# DCDC-LMR16030.net
KiCad netlist of a schematic drawn in Altium Designer
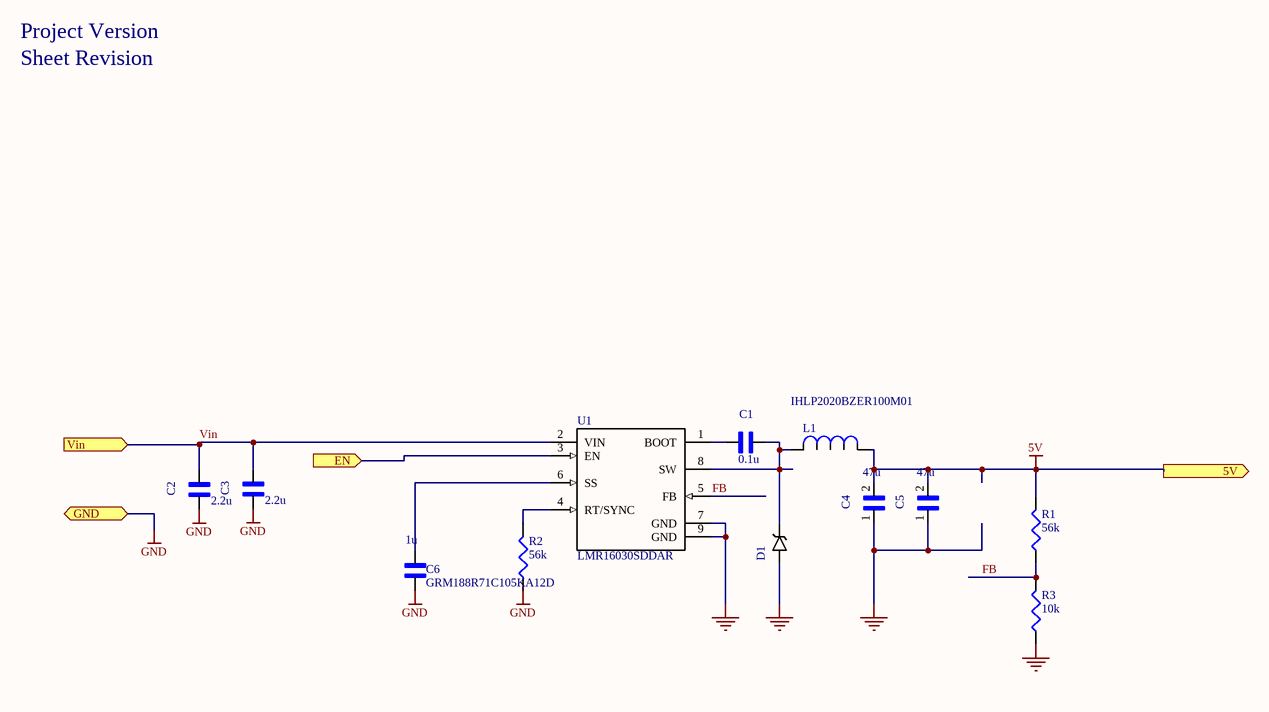
[diagram p0: DCDC-LMR16030.SchDoc]

(export (version "E")
  (design (tool "Eeschema 10.0.6"))
  (components
    (comp (ref "C1")
      (value "0.1u")
      (footprint "*CAPC1608X90")
      (description "Cap Thin Film 0.1uf 50v 0603")
      (fields (field (name "MF") "AVX") (field (name "MP") "GX035C104MAT2-500 or CL10B104JB8NNNC"))
      (libsource (lib "lib") (part "GX035C104MAT2-500"))
    )
    (comp (ref "C2")
      (value "2.2u")
      (footprint "*CAP3216X125N")
      (description "1206 2.2 uF 50 V В±10% Tolerance X7R SMT Multilayer Ceramic Capacitor")
      (fields (field (name "MF") "Murata Electronics") (field (name "MP") "GRM31CR71H225KA88L"))
      (libsource (lib "lib") (part "GRM31CR71H225KA88L"))
    )
    (comp (ref "C3")
      (value "2.2u")
      (footprint "*CAP3216X125N")
      (description "1206 2.2 uF 50 V В±10% Tolerance X7R SMT Multilayer Ceramic Capacitor")
      (fields (field (name "MF") "Murata Electronics") (field (name "MP") "GRM31CR71H225KA88L"))
      (libsource (lib "lib") (part "GRM31CR71H225KA88L"))
    )
    (comp (ref "C4")
      (value "47u")
      (footprint "*CAPC3216X125N")
      (description "Multilayer Ceramic Capacitor, GRM Series, 47 - F, - 10%, X5R, 10 V, 1206 [3216 Metric]")
      (fields (field (name "MF") "Murata Electronics") (field (name "MP") "GRM31CR61A476KE15L"))
      (libsource (lib "lib") (part "GRM31CR61A476KE15L"))
    )
    (comp (ref "C5")
      (value "47u")
      (footprint "*CAPC3216X125N")
      (description "Multilayer Ceramic Capacitor, GRM Series, 47 - F, - 10%, X5R, 10 V, 1206 [3216 Metric]")
      (fields (field (name "MF") "Murata Electronics") (field (name "MP") "GRM31CR61A476KE15L"))
      (libsource (lib "lib") (part "GRM31CR61A476KE15L"))
    )
    (comp (ref "C6")
      (value "GRM188R71C105KA12D")
      (footprint "CAPC1608X90N")
      (description "SMD Capacitor X7R(EIA) with Capacitance: 1.0uF Tol. 10%. Rated Voltage: 16Vdc")
      (fields (field (name "MF") "Murata Electronics") (field (name "ALTIUM_VALUE") "1u"))
      (libsource (lib "lib") (part "GRM188R71C105KA12D"))
    )
    (comp (ref "D1")
      (value "SK56")
      (footprint "*SMB_P6SMB62AT3G(Primary)")
      (description "Диод Шоттки 5А 60В [SMB / DO-214AA]")
      (fields (field (name "MF") "Littelfuse Inc."))
      (libsource (lib "lib") (part "SK56"))
    )
    (comp (ref "L1")
      (value "IHLP2020BZER100M01")
      (footprint "IHLP")
      (description "10ÂµH Shielded Molded Inductor 2.3A 199mOhm Max Nonstandard")
      (fields (field (name "MF") "Vishay Dale"))
      (libsource (lib "lib") (part "IHLP2020BZER100M01"))
    )
    (comp (ref "R1")
      (value "56k")
      (footprint "J1-0603")
      (description "Resistor")
      (fields (field (name "MP") "RC0603FR-0756KL") (field (name "Comment") "Res3"))
      (libsource (lib "Miscellaneous Devices") (part "Res3"))
    )
    (comp (ref "R2")
      (value "56k")
      (footprint "J1-0603")
      (description "Resistor")
      (fields (field (name "MP") "RC0603FR-0756KL") (field (name "Comment") "Res3"))
      (libsource (lib "Miscellaneous Devices") (part "Res3"))
    )
    (comp (ref "R3")
      (value "10k")
      (footprint "J1-0603")
      (description "10 kOhms 1 0.1 W 1 10 W Chip Resistor 0603 1608 Metric Thick Film")
      (fields (field (name "MF") "Yageo or NXP") (field (name "MP") "10K 1% 0603"))
      (libsource (lib "CAN_NODE_MINI") (part "RC0603FR-0710KL"))
    )
    (comp (ref "U1")
      (value "LMR16030SDDAR")
      (footprint "*SOIC127P600X170-9N - duplicate")
      (fields (field (name "MF") "Texas Instruments"))
      (libsource (lib "lib") (part "LMR16030SDDAR"))
    )
  )
  (nets
    (net (code "1") (name "/EN") (class "Default")
      (node (ref "U1") (pin "3") (pinfunction "EN_3") (pintype "input"))
    )
    (net (code "2") (name "/FB") (class "Default")
      (node (ref "R1") (pin "1") (pinfunction "1_1") (pintype "passive"))
      (node (ref "R3") (pin "2") (pinfunction "2_2") (pintype "passive"))
      (node (ref "U1") (pin "5") (pinfunction "FB_5") (pintype "input"))
    )
    (net (code "3") (name "/Vin") (class "Default")
      (node (ref "C2") (pin "1") (pinfunction "1_1") (pintype "passive"))
      (node (ref "C3") (pin "1") (pinfunction "1_1") (pintype "passive"))
      (node (ref "U1") (pin "2") (pinfunction "VIN_2") (pintype "power_in"))
    )
    (net (code "4") (name "5V") (class "Default")
      (node (ref "C4") (pin "2") (pinfunction "2_2") (pintype "passive"))
      (node (ref "C5") (pin "2") (pinfunction "2_2") (pintype "passive"))
      (node (ref "L1") (pin "1") (pinfunction "1_1") (pintype "passive"))
      (node (ref "R1") (pin "2") (pinfunction "2_2") (pintype "passive"))
    )
    (net (code "5") (name "GND") (class "Default")
      (node (ref "C2") (pin "2") (pinfunction "2_2") (pintype "passive"))
      (node (ref "C3") (pin "2") (pinfunction "2_2") (pintype "passive"))
      (node (ref "C4") (pin "1") (pinfunction "1_1") (pintype "passive"))
      (node (ref "C5") (pin "1") (pinfunction "1_1") (pintype "passive"))
      (node (ref "C6") (pin "1") (pinfunction "1_1") (pintype "passive"))
      (node (ref "D1") (pin "A") (pinfunction "A_A") (pintype "power_in"))
      (node (ref "R2") (pin "1") (pinfunction "1_1") (pintype "passive"))
      (node (ref "R3") (pin "1") (pinfunction "1_1") (pintype "passive"))
      (node (ref "U1") (pin "7") (pinfunction "GND_7") (pintype "power_in"))
      (node (ref "U1") (pin "9") (pinfunction "GND_9") (pintype "power_in"))
    )
    (net (code "6") (name "Net-(U1-BOOT)") (class "Default")
      (node (ref "C1") (pin "2") (pinfunction "2_2") (pintype "passive"))
      (node (ref "U1") (pin "1") (pinfunction "BOOT_1") (pintype "power_in"))
    )
    (net (code "7") (name "Net-(U1-RT{slash}SYNC)") (class "Default")
      (node (ref "R2") (pin "2") (pinfunction "2_2") (pintype "passive"))
      (node (ref "U1") (pin "4") (pinfunction "RT/SYNC_4") (pintype "input"))
    )
    (net (code "8") (name "Net-(U1-SS)") (class "Default")
      (node (ref "C6") (pin "2") (pinfunction "2_2") (pintype "passive"))
      (node (ref "U1") (pin "6") (pinfunction "SS_6") (pintype "input"))
    )
    (net (code "9") (name "Net-(U1-SW)") (class "Default")
      (node (ref "C1") (pin "1") (pinfunction "1_1") (pintype "passive"))
      (node (ref "D1") (pin "C") (pinfunction "C_C") (pintype "power_in"))
      (node (ref "L1") (pin "2") (pinfunction "2_2") (pintype "passive"))
      (node (ref "U1") (pin "8") (pinfunction "SW_8") (pintype "power_in"))
    )
  )
)
